# PWM_CONTROL.net
KiCad netlist of a schematic drawn in Altium Designer
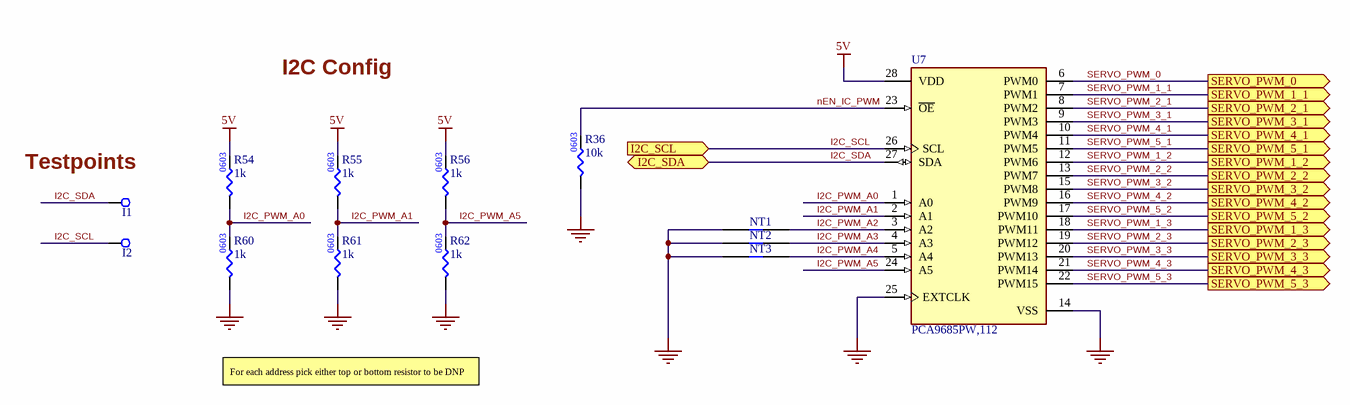
[diagram p0: PWM_CONTROL.SchDoc]

(export (version "E")
  (design (tool "Eeschema 10.0.6"))
  (components
    (comp (ref "I1")
      (value "RCWCTE")
      (footprint "RCWCTE")
      (description "SMT Test Point")
      (fields (field (name "MANUFACTURER") "KOA Speer"))
      (libsource (lib "PuttPilot") (part "RCWCTE"))
    )
    (comp (ref "I2")
      (value "RCWCTE")
      (footprint "RCWCTE")
      (description "SMT Test Point")
      (fields (field (name "MANUFACTURER") "KOA Speer"))
      (libsource (lib "PuttPilot") (part "RCWCTE"))
    )
    (comp (ref "NT1")
      (value ".NET_TIE")
      (footprint ".NET_TIE")
      (description ".GENERIC NET TIE")
      (libsource (lib "PuttPilot") (part ".NET_TIE"))
    )
    (comp (ref "NT2")
      (value ".NET_TIE")
      (footprint ".NET_TIE")
      (description ".GENERIC NET TIE")
      (libsource (lib "PuttPilot") (part ".NET_TIE"))
    )
    (comp (ref "NT3")
      (value ".NET_TIE")
      (footprint ".NET_TIE")
      (description ".GENERIC NET TIE")
      (libsource (lib "PuttPilot") (part ".NET_TIE"))
    )
    (comp (ref "R36")
      (value "RC0603FR-0710KL")
      (footprint ".RES_0603")
      (description "RES 10K OHM 0603")
      (fields
        (field (name "MANUFACTURER") "Yageo")
        (field (name "TOLERANCE") "1%")
        (field (name "RESISTANCE") "10k")
      )
      (libsource (lib "PuttPilot") (part "RC0603FR-0710KL"))
    )
    (comp (ref "R54")
      (value "RC0603FR-071KL")
      (footprint ".RES_0603")
      (description "RES 1K OHM 0603")
      (fields
        (field (name "MANUFACTURER") "Yageo")
        (field (name "TOLERANCE") "1%")
        (field (name "RESISTANCE") "1k")
      )
      (libsource (lib "PuttPilot") (part "RC0603FR-071KL"))
    )
    (comp (ref "R55")
      (value "RC0603FR-071KL")
      (footprint ".RES_0603")
      (description "RES 1K OHM 0603")
      (fields
        (field (name "MANUFACTURER") "Yageo")
        (field (name "TOLERANCE") "1%")
        (field (name "RESISTANCE") "1k")
      )
      (libsource (lib "PuttPilot") (part "RC0603FR-071KL"))
    )
    (comp (ref "R56")
      (value "RC0603FR-071KL")
      (footprint ".RES_0603")
      (description "RES 1K OHM 0603")
      (fields
        (field (name "MANUFACTURER") "Yageo")
        (field (name "TOLERANCE") "1%")
        (field (name "RESISTANCE") "1k")
      )
      (libsource (lib "PuttPilot") (part "RC0603FR-071KL"))
    )
    (comp (ref "R60")
      (value "RC0603FR-071KL")
      (footprint ".RES_0603")
      (description "RES 1K OHM 0603")
      (fields
        (field (name "MANUFACTURER") "Yageo")
        (field (name "TOLERANCE") "1%")
        (field (name "RESISTANCE") "1k")
      )
      (libsource (lib "PuttPilot") (part "RC0603FR-071KL"))
    )
    (comp (ref "R61")
      (value "RC0603FR-071KL")
      (footprint ".RES_0603")
      (description "RES 1K OHM 0603")
      (fields
        (field (name "MANUFACTURER") "Yageo")
        (field (name "TOLERANCE") "1%")
        (field (name "RESISTANCE") "1k")
      )
      (libsource (lib "PuttPilot") (part "RC0603FR-071KL"))
    )
    (comp (ref "R62")
      (value "RC0603FR-071KL")
      (footprint ".RES_0603")
      (description "RES 1K OHM 0603")
      (fields
        (field (name "MANUFACTURER") "Yageo")
        (field (name "TOLERANCE") "1%")
        (field (name "RESISTANCE") "1k")
      )
      (libsource (lib "PuttPilot") (part "RC0603FR-071KL"))
    )
    (comp (ref "U7")
      (value "PCA9685PW,112")
      (footprint "PCA9685PW,112")
      (description "I2C LED Driver")
      (fields (field (name "MANUFACTURER") "NXP Semiconductors"))
      (libsource (lib "PuttPilot") (part "PCA9685PW,112"))
    )
  )
  (nets
    (net (code "1") (name "/I2C_PWM_A0") (class "Default")
      (node (ref "R54") (pin "1") (pinfunction "1_1") (pintype "passive"))
      (node (ref "R60") (pin "2") (pinfunction "2_2") (pintype "passive"))
      (node (ref "U7") (pin "1") (pinfunction "A0_1") (pintype "input"))
    )
    (net (code "2") (name "/I2C_PWM_A1") (class "Default")
      (node (ref "R55") (pin "1") (pinfunction "1_1") (pintype "passive"))
      (node (ref "R61") (pin "2") (pinfunction "2_2") (pintype "passive"))
      (node (ref "U7") (pin "2") (pinfunction "A1_2") (pintype "input"))
    )
    (net (code "3") (name "/I2C_PWM_A2") (class "Default")
      (node (ref "NT1") (pin "2") (pinfunction "2_2") (pintype "passive"))
      (node (ref "U7") (pin "3") (pinfunction "A2_3") (pintype "input"))
    )
    (net (code "4") (name "/I2C_PWM_A3") (class "Default")
      (node (ref "NT2") (pin "2") (pinfunction "2_2") (pintype "passive"))
      (node (ref "U7") (pin "4") (pinfunction "A3_4") (pintype "input"))
    )
    (net (code "5") (name "/I2C_PWM_A4") (class "Default")
      (node (ref "NT3") (pin "2") (pinfunction "2_2") (pintype "passive"))
      (node (ref "U7") (pin "5") (pinfunction "A4_5") (pintype "input"))
    )
    (net (code "6") (name "/I2C_PWM_A5") (class "Default")
      (node (ref "R56") (pin "1") (pinfunction "1_1") (pintype "passive"))
      (node (ref "R62") (pin "2") (pinfunction "2_2") (pintype "passive"))
      (node (ref "U7") (pin "24") (pinfunction "A5_24") (pintype "input"))
    )
    (net (code "7") (name "/I2C_SCL") (class "Default")
      (node (ref "I2") (pin "1") (pinfunction "1_1") (pintype "passive"))
      (node (ref "U7") (pin "26") (pinfunction "SCL_26") (pintype "input"))
    )
    (net (code "8") (name "/I2C_SDA") (class "Default")
      (node (ref "I1") (pin "1") (pinfunction "1_1") (pintype "passive"))
      (node (ref "U7") (pin "27") (pinfunction "SDA_27") (pintype "bidirectional"))
    )
    (net (code "9") (name "/SERVO_PWM_0") (class "Default")
      (node (ref "U7") (pin "6") (pinfunction "PWM0_6") (pintype "tri_state"))
    )
    (net (code "10") (name "/SERVO_PWM_1_1") (class "Default")
      (node (ref "U7") (pin "7") (pinfunction "PWM1_7") (pintype "tri_state"))
    )
    (net (code "11") (name "/SERVO_PWM_1_2") (class "Default")
      (node (ref "U7") (pin "12") (pinfunction "PWM6_12") (pintype "tri_state"))
    )
    (net (code "12") (name "/SERVO_PWM_1_3") (class "Default")
      (node (ref "U7") (pin "18") (pinfunction "PWM11_18") (pintype "tri_state"))
    )
    (net (code "13") (name "/SERVO_PWM_2_1") (class "Default")
      (node (ref "U7") (pin "8") (pinfunction "PWM2_8") (pintype "tri_state"))
    )
    (net (code "14") (name "/SERVO_PWM_2_2") (class "Default")
      (node (ref "U7") (pin "13") (pinfunction "PWM7_13") (pintype "tri_state"))
    )
    (net (code "15") (name "/SERVO_PWM_2_3") (class "Default")
      (node (ref "U7") (pin "19") (pinfunction "PWM12_19") (pintype "tri_state"))
    )
    (net (code "16") (name "/SERVO_PWM_3_1") (class "Default")
      (node (ref "U7") (pin "9") (pinfunction "PWM3_9") (pintype "tri_state"))
    )
    (net (code "17") (name "/SERVO_PWM_3_2") (class "Default")
      (node (ref "U7") (pin "15") (pinfunction "PWM8_15") (pintype "tri_state"))
    )
    (net (code "18") (name "/SERVO_PWM_3_3") (class "Default")
      (node (ref "U7") (pin "20") (pinfunction "PWM13_20") (pintype "tri_state"))
    )
    (net (code "19") (name "/SERVO_PWM_4_1") (class "Default")
      (node (ref "U7") (pin "10") (pinfunction "PWM4_10") (pintype "tri_state"))
    )
    (net (code "20") (name "/SERVO_PWM_4_2") (class "Default")
      (node (ref "U7") (pin "16") (pinfunction "PWM9_16") (pintype "tri_state"))
    )
    (net (code "21") (name "/SERVO_PWM_4_3") (class "Default")
      (node (ref "U7") (pin "21") (pinfunction "PWM14_21") (pintype "tri_state"))
    )
    (net (code "22") (name "/SERVO_PWM_5_1") (class "Default")
      (node (ref "U7") (pin "11") (pinfunction "PWM5_11") (pintype "tri_state"))
    )
    (net (code "23") (name "/SERVO_PWM_5_2") (class "Default")
      (node (ref "U7") (pin "17") (pinfunction "PWM10_17") (pintype "tri_state"))
    )
    (net (code "24") (name "/SERVO_PWM_5_3") (class "Default")
      (node (ref "U7") (pin "22") (pinfunction "PWM15_22") (pintype "tri_state"))
    )
    (net (code "25") (name "/nEN_IC_PWM") (class "Default")
      (node (ref "R36") (pin "2") (pinfunction "2_2") (pintype "passive"))
      (node (ref "U7") (pin "23") (pinfunction "~{OE}_23") (pintype "input"))
    )
    (net (code "26") (name "5V") (class "Default")
      (node (ref "R54") (pin "2") (pinfunction "2_2") (pintype "passive"))
      (node (ref "R55") (pin "2") (pinfunction "2_2") (pintype "passive"))
      (node (ref "R56") (pin "2") (pinfunction "2_2") (pintype "passive"))
      (node (ref "U7") (pin "28") (pinfunction "VDD_28") (pintype "power_in"))
    )
    (net (code "27") (name "GND") (class "Default")
      (node (ref "NT1") (pin "1") (pinfunction "1_1") (pintype "passive"))
      (node (ref "NT2") (pin "1") (pinfunction "1_1") (pintype "passive"))
      (node (ref "NT3") (pin "1") (pinfunction "1_1") (pintype "passive"))
      (node (ref "R36") (pin "1") (pinfunction "1_1") (pintype "passive"))
      (node (ref "R60") (pin "1") (pinfunction "1_1") (pintype "passive"))
      (node (ref "R61") (pin "1") (pinfunction "1_1") (pintype "passive"))
      (node (ref "R62") (pin "1") (pinfunction "1_1") (pintype "passive"))
      (node (ref "U7") (pin "14") (pinfunction "VSS_14") (pintype "power_in"))
      (node (ref "U7") (pin "25") (pinfunction "EXTCLK_25") (pintype "input"))
    )
  )
)
